# RaspberryPi.net
KiCad netlist of a schematic drawn in Altium Designer
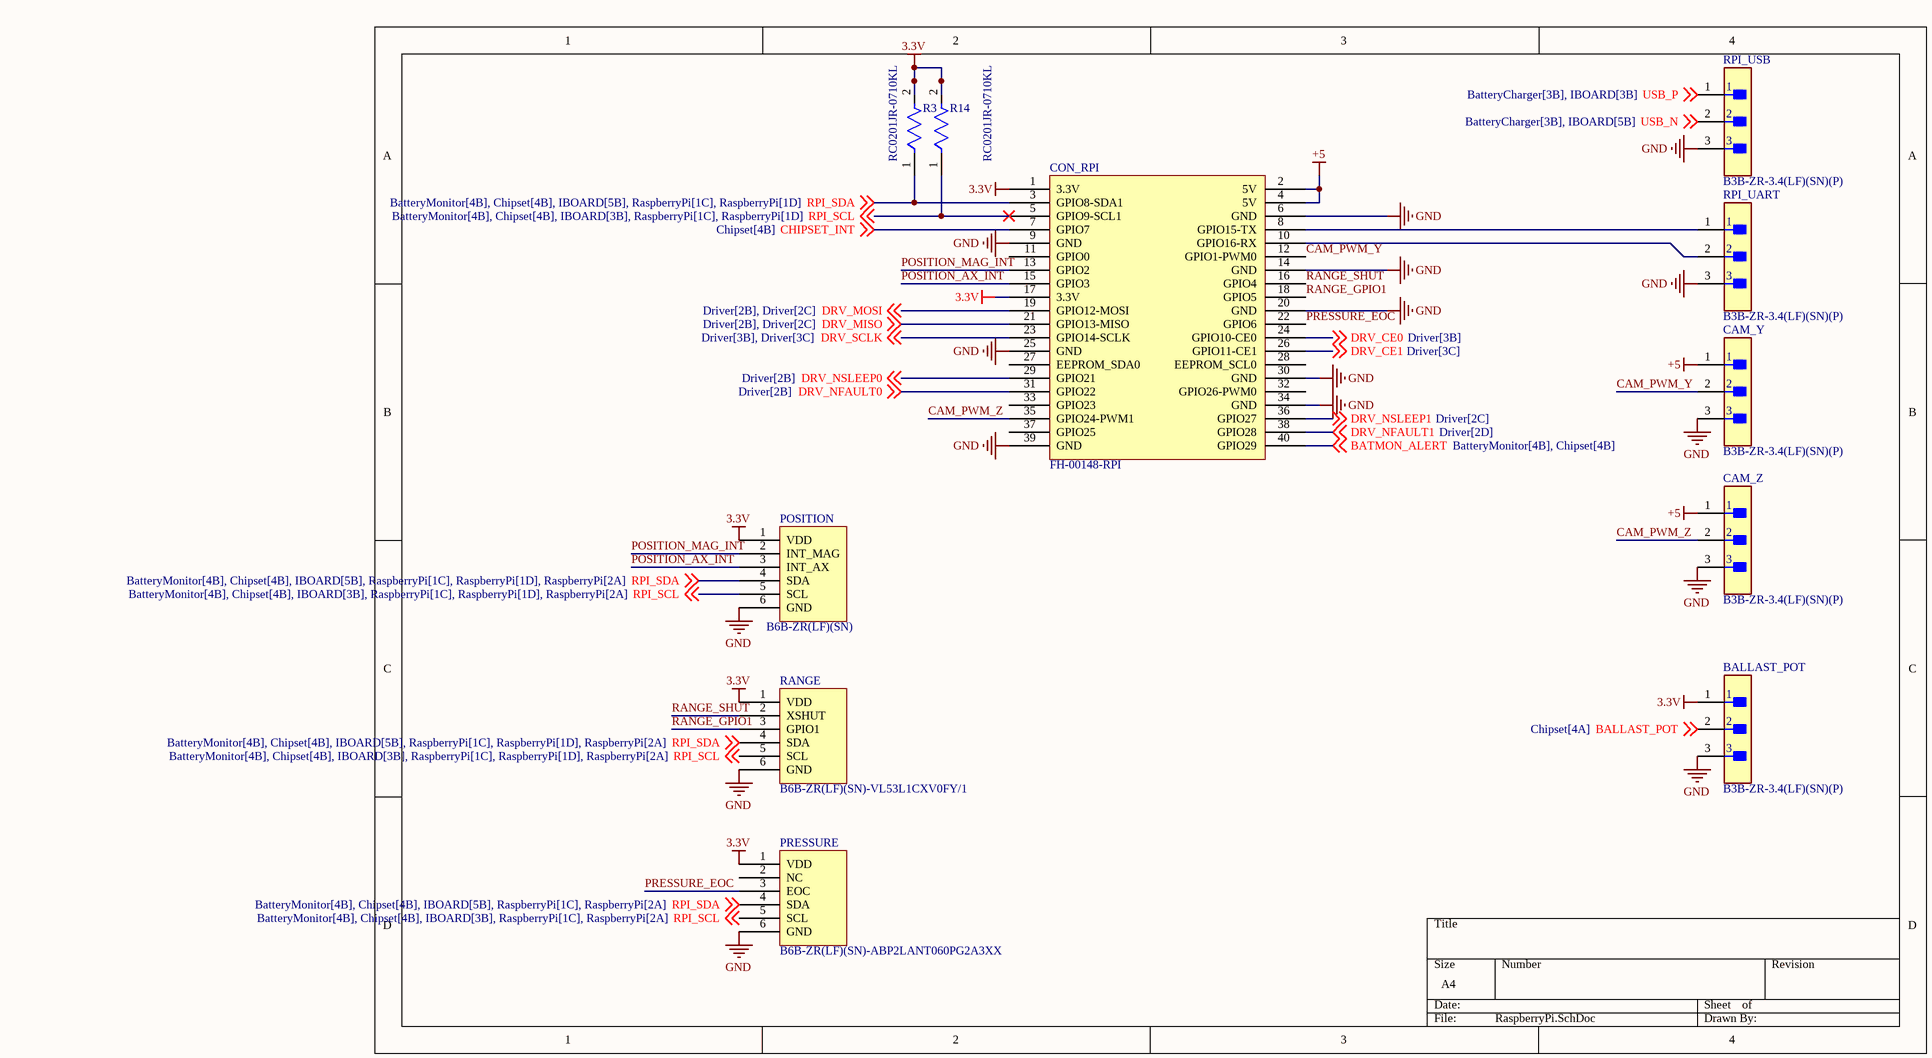
[diagram p0: RaspberryPi.SchDoc]

(export (version "E")
  (design (tool "Eeschema 10.0.6"))
  (components
    (comp (ref "BALLAST_POT")
      (value "B3B-ZR-3.4(LF)(SN)(P)")
      (footprint "FP-B3B-ZR-3_4_LF_SN_P-MFG")
      (description "CONN HEADER VERT 3POS 1.5MM")
      (libsource (lib "Altium Content Vault") (part "0d3f023dd272f625e17a2be33dea85f"))
    )
    (comp (ref "CAM_Y")
      (value "B3B-ZR-3.4(LF)(SN)(P)")
      (footprint "FP-B3B-ZR-3_4_LF_SN_P-MFG")
      (description "CONN HEADER VERT 3POS 1.5MM")
      (libsource (lib "Altium Content Vault") (part "0d3f023dd272f625e17a2be33dea85f"))
    )
    (comp (ref "CAM_Z")
      (value "B3B-ZR-3.4(LF)(SN)(P)")
      (footprint "FP-B3B-ZR-3_4_LF_SN_P-MFG")
      (description "CONN HEADER VERT 3POS 1.5MM")
      (libsource (lib "Altium Content Vault") (part "0d3f023dd272f625e17a2be33dea85f"))
    )
    (comp (ref "CON_RPI")
      (value "FH-00148-RPI")
      (footprint "FH-00148")
      (libsource (lib "FH-00148") (part "FH-00148-RPI"))
    )
    (comp (ref "POSITION")
      (value "B6B-ZR(LF)(SN)")
      (footprint "B6B-ZR(LF)(SN)")
      (libsource (lib "B6B-ZR(LF)(SN)") (part "B6B-ZR(LF)(SN)-LSM303AGRTR"))
    )
    (comp (ref "PRESSURE")
      (value "B6B-ZR(LF)(SN)-ABP2LANT060PG2A3XX")
      (footprint "B6B-ZR(LF)(SN)")
      (libsource (lib "B6B-ZR(LF)(SN)") (part "B6B-ZR(LF)(SN)-ABP2LANT060PG2A3XX"))
    )
    (comp (ref "R3")
      (value "RC0201JR-0710KL")
      (footprint "FP-RC0201-0_26-IPC_C")
      (description "RES SMD 10K OHM 5% 1/20W 0201")
      (fields (field (name "TOLERANCE") "5%"))
      (libsource (lib "Altium Content Vault") (part "1029c3af85768c4190bb7ad29bc67b5"))
    )
    (comp (ref "R14")
      (value "RC0201JR-0710KL")
      (footprint "FP-RC0201-0_26-IPC_C")
      (description "RES SMD 10K OHM 5% 1/20W 0201")
      (fields (field (name "TOLERANCE") "5%"))
      (libsource (lib "Altium Content Vault") (part "1029c3af85768c4190bb7ad29bc67b5"))
    )
    (comp (ref "RANGE")
      (value "B6B-ZR(LF)(SN)-VL53L1CXV0FY/1")
      (footprint "B6B-ZR(LF)(SN)")
      (libsource (lib "B6B-ZR(LF)(SN)") (part "B6B-ZR(LF)(SN)-VL53L1CXV0FY/1"))
    )
    (comp (ref "RPI_UART")
      (value "B3B-ZR-3.4(LF)(SN)(P)")
      (footprint "FP-B3B-ZR-3_4_LF_SN_P-MFG")
      (description "CONN HEADER VERT 3POS 1.5MM")
      (libsource (lib "Altium Content Vault") (part "0d3f023dd272f625e17a2be33dea85f"))
    )
    (comp (ref "RPI_USB")
      (value "B3B-ZR-3.4(LF)(SN)(P)")
      (footprint "FP-B3B-ZR-3_4_LF_SN_P-MFG")
      (description "CONN HEADER VERT 3POS 1.5MM")
      (libsource (lib "Altium Content Vault") (part "0d3f023dd272f625e17a2be33dea85f"))
    )
  )
  (nets
    (net (code "1") (name "+5") (class "Default")
      (node (ref "CAM_Y") (pin "1") (pinfunction "1_1") (pintype "passive"))
      (node (ref "CAM_Z") (pin "1") (pinfunction "1_1") (pintype "passive"))
      (node (ref "CON_RPI") (pin "2") (pinfunction "5V_2") (pintype "passive"))
      (node (ref "CON_RPI") (pin "4") (pinfunction "5V_4") (pintype "passive"))
    )
    (net (code "2") (name "/CAM_PWM_Y") (class "Default")
      (node (ref "CAM_Y") (pin "2") (pinfunction "2_2") (pintype "passive"))
      (node (ref "CON_RPI") (pin "12") (pinfunction "GPIO1-PWM0_12") (pintype "passive"))
    )
    (net (code "3") (name "/CAM_PWM_Z") (class "Default")
      (node (ref "CAM_Z") (pin "2") (pinfunction "2_2") (pintype "passive"))
      (node (ref "CON_RPI") (pin "35") (pinfunction "GPIO24-PWM1_35") (pintype "passive"))
    )
    (net (code "4") (name "/POSITION_AX_INT") (class "Default")
      (node (ref "CON_RPI") (pin "15") (pinfunction "GPIO3_15") (pintype "passive"))
      (node (ref "POSITION") (pin "3") (pinfunction "INT_AX_3") (pintype "passive"))
    )
    (net (code "5") (name "/POSITION_MAG_INT") (class "Default")
      (node (ref "CON_RPI") (pin "13") (pinfunction "GPIO2_13") (pintype "passive"))
      (node (ref "POSITION") (pin "2") (pinfunction "INT_MAG_2") (pintype "passive"))
    )
    (net (code "6") (name "/PRESSURE_EOC") (class "Default")
      (node (ref "CON_RPI") (pin "22") (pinfunction "GPIO6_22") (pintype "passive"))
      (node (ref "PRESSURE") (pin "3") (pinfunction "EOC_3") (pintype "passive"))
    )
    (net (code "7") (name "/RANGE_GPIO1") (class "Default")
      (node (ref "CON_RPI") (pin "18") (pinfunction "GPIO5_18") (pintype "passive"))
      (node (ref "RANGE") (pin "3") (pinfunction "GPIO1_3") (pintype "passive"))
    )
    (net (code "8") (name "/RANGE_SHUT") (class "Default")
      (node (ref "CON_RPI") (pin "16") (pinfunction "GPIO4_16") (pintype "passive"))
      (node (ref "RANGE") (pin "2") (pinfunction "XSHUT_2") (pintype "passive"))
    )
    (net (code "9") (name "3.3V") (class "Default")
      (node (ref "BALLAST_POT") (pin "1") (pinfunction "1_1") (pintype "passive"))
      (node (ref "CON_RPI") (pin "1") (pinfunction "3.3V_1") (pintype "passive"))
      (node (ref "CON_RPI") (pin "17") (pinfunction "3.3V_17") (pintype "passive"))
      (node (ref "POSITION") (pin "1") (pinfunction "VDD_1") (pintype "passive"))
      (node (ref "PRESSURE") (pin "1") (pinfunction "VDD_1") (pintype "passive"))
      (node (ref "R14") (pin "2") (pinfunction "2_2") (pintype "passive"))
      (node (ref "R3") (pin "2") (pinfunction "2_2") (pintype "passive"))
      (node (ref "RANGE") (pin "1") (pinfunction "VDD_1") (pintype "passive"))
    )
    (net (code "10") (name "BALLAST_POT") (class "Default")
      (node (ref "BALLAST_POT") (pin "2") (pinfunction "2_2") (pintype "passive"))
    )
    (net (code "11") (name "BATMON_ALERT") (class "Default")
      (node (ref "CON_RPI") (pin "40") (pinfunction "GPIO29_40") (pintype "passive"))
    )
    (net (code "12") (name "CHIPSET_INT") (class "Default")
      (node (ref "CON_RPI") (pin "7") (pinfunction "GPIO7_7") (pintype "passive"))
    )
    (net (code "13") (name "DRV_CE0") (class "Default")
      (node (ref "CON_RPI") (pin "24") (pinfunction "GPIO10-CE0_24") (pintype "passive"))
    )
    (net (code "14") (name "DRV_CE1") (class "Default")
      (node (ref "CON_RPI") (pin "26") (pinfunction "GPIO11-CE1_26") (pintype "passive"))
    )
    (net (code "15") (name "DRV_MISO") (class "Default")
      (node (ref "CON_RPI") (pin "21") (pinfunction "GPIO13-MISO_21") (pintype "passive"))
    )
    (net (code "16") (name "DRV_MOSI") (class "Default")
      (node (ref "CON_RPI") (pin "19") (pinfunction "GPIO12-MOSI_19") (pintype "passive"))
    )
    (net (code "17") (name "DRV_NFAULT0") (class "Default")
      (node (ref "CON_RPI") (pin "31") (pinfunction "GPIO22_31") (pintype "passive"))
    )
    (net (code "18") (name "DRV_NFAULT1") (class "Default")
      (node (ref "CON_RPI") (pin "38") (pinfunction "GPIO28_38") (pintype "passive"))
    )
    (net (code "19") (name "DRV_NSLEEP0") (class "Default")
      (node (ref "CON_RPI") (pin "29") (pinfunction "GPIO21_29") (pintype "passive"))
    )
    (net (code "20") (name "DRV_NSLEEP1") (class "Default")
      (node (ref "CON_RPI") (pin "36") (pinfunction "GPIO27_36") (pintype "passive"))
    )
    (net (code "21") (name "DRV_SCLK") (class "Default")
      (node (ref "CON_RPI") (pin "23") (pinfunction "GPIO14-SCLK_23") (pintype "passive"))
    )
    (net (code "22") (name "GND") (class "Default")
      (node (ref "BALLAST_POT") (pin "3") (pinfunction "3_3") (pintype "passive"))
      (node (ref "CAM_Y") (pin "3") (pinfunction "3_3") (pintype "passive"))
      (node (ref "CAM_Z") (pin "3") (pinfunction "3_3") (pintype "passive"))
      (node (ref "CON_RPI") (pin "14") (pinfunction "GND_14") (pintype "passive"))
      (node (ref "CON_RPI") (pin "20") (pinfunction "GND_20") (pintype "passive"))
      (node (ref "CON_RPI") (pin "25") (pinfunction "GND_25") (pintype "passive"))
      (node (ref "CON_RPI") (pin "30") (pinfunction "GND_30") (pintype "passive"))
      (node (ref "CON_RPI") (pin "34") (pinfunction "GND_34") (pintype "passive"))
      (node (ref "CON_RPI") (pin "39") (pinfunction "GND_39") (pintype "passive"))
      (node (ref "CON_RPI") (pin "6") (pinfunction "GND_6") (pintype "passive"))
      (node (ref "CON_RPI") (pin "9") (pinfunction "GND_9") (pintype "passive"))
      (node (ref "POSITION") (pin "6") (pinfunction "GND_6") (pintype "passive"))
      (node (ref "PRESSURE") (pin "6") (pinfunction "GND_6") (pintype "passive"))
      (node (ref "RANGE") (pin "6") (pinfunction "GND_6") (pintype "passive"))
      (node (ref "RPI_UART") (pin "3") (pinfunction "3_3") (pintype "passive"))
      (node (ref "RPI_USB") (pin "3") (pinfunction "3_3") (pintype "passive"))
    )
    (net (code "23") (name "Net-(CON_RPI-GPIO15-TX)") (class "Default")
      (node (ref "CON_RPI") (pin "8") (pinfunction "GPIO15-TX_8") (pintype "passive"))
      (node (ref "RPI_UART") (pin "1") (pinfunction "1_1") (pintype "passive"))
    )
    (net (code "24") (name "Net-(CON_RPI-GPIO16-RX)") (class "Default")
      (node (ref "CON_RPI") (pin "10") (pinfunction "GPIO16-RX_10") (pintype "passive"))
      (node (ref "RPI_UART") (pin "2") (pinfunction "2_2") (pintype "passive"))
    )
    (net (code "25") (name "RPI_SCL") (class "Default")
      (node (ref "CON_RPI") (pin "5") (pinfunction "GPIO9-SCL1_5") (pintype "passive"))
      (node (ref "POSITION") (pin "5") (pinfunction "SCL_5") (pintype "passive"))
      (node (ref "PRESSURE") (pin "5") (pinfunction "SCL_5") (pintype "passive"))
      (node (ref "R14") (pin "1") (pinfunction "1_1") (pintype "passive"))
      (node (ref "RANGE") (pin "5") (pinfunction "SCL_5") (pintype "passive"))
    )
    (net (code "26") (name "RPI_SDA") (class "Default")
      (node (ref "CON_RPI") (pin "3") (pinfunction "GPIO8-SDA1_3") (pintype "passive"))
      (node (ref "POSITION") (pin "4") (pinfunction "SDA_4") (pintype "passive"))
      (node (ref "PRESSURE") (pin "4") (pinfunction "SDA_4") (pintype "passive"))
      (node (ref "R3") (pin "1") (pinfunction "1_1") (pintype "passive"))
      (node (ref "RANGE") (pin "4") (pinfunction "SDA_4") (pintype "passive"))
    )
    (net (code "27") (name "USB_N") (class "Default")
      (node (ref "RPI_USB") (pin "2") (pinfunction "2_2") (pintype "passive"))
    )
    (net (code "28") (name "USB_P") (class "Default")
      (node (ref "RPI_USB") (pin "1") (pinfunction "1_1") (pintype "passive"))
    )
    (net (code "29") (name "unconnected-(CON_RPI-EEPROM_SCL0-Pad28)") (class "Default")
      (node (ref "CON_RPI") (pin "28") (pinfunction "EEPROM_SCL0_28") (pintype "passive"))
    )
    (net (code "30") (name "unconnected-(CON_RPI-EEPROM_SDA0-Pad27)") (class "Default")
      (node (ref "CON_RPI") (pin "27") (pinfunction "EEPROM_SDA0_27") (pintype "passive"))
    )
    (net (code "31") (name "unconnected-(CON_RPI-GPIO0-Pad11)") (class "Default")
      (node (ref "CON_RPI") (pin "11") (pinfunction "GPIO0_11") (pintype "passive"))
    )
    (net (code "32") (name "unconnected-(CON_RPI-GPIO23-Pad33)") (class "Default")
      (node (ref "CON_RPI") (pin "33") (pinfunction "GPIO23_33") (pintype "passive"))
    )
    (net (code "33") (name "unconnected-(CON_RPI-GPIO25-Pad37)") (class "Default")
      (node (ref "CON_RPI") (pin "37") (pinfunction "GPIO25_37") (pintype "passive"))
    )
    (net (code "34") (name "unconnected-(CON_RPI-GPIO26-PWM0-Pad32)") (class "Default")
      (node (ref "CON_RPI") (pin "32") (pinfunction "GPIO26-PWM0_32") (pintype "passive"))
    )
    (net (code "35") (name "unconnected-(PRESSURE-NC-Pad2)") (class "Default")
      (node (ref "PRESSURE") (pin "2") (pinfunction "NC_2") (pintype "passive"))
    )
  )
)
